# atmega2560-power_planes.net
KiCad netlist of a schematic drawn in EAGLE
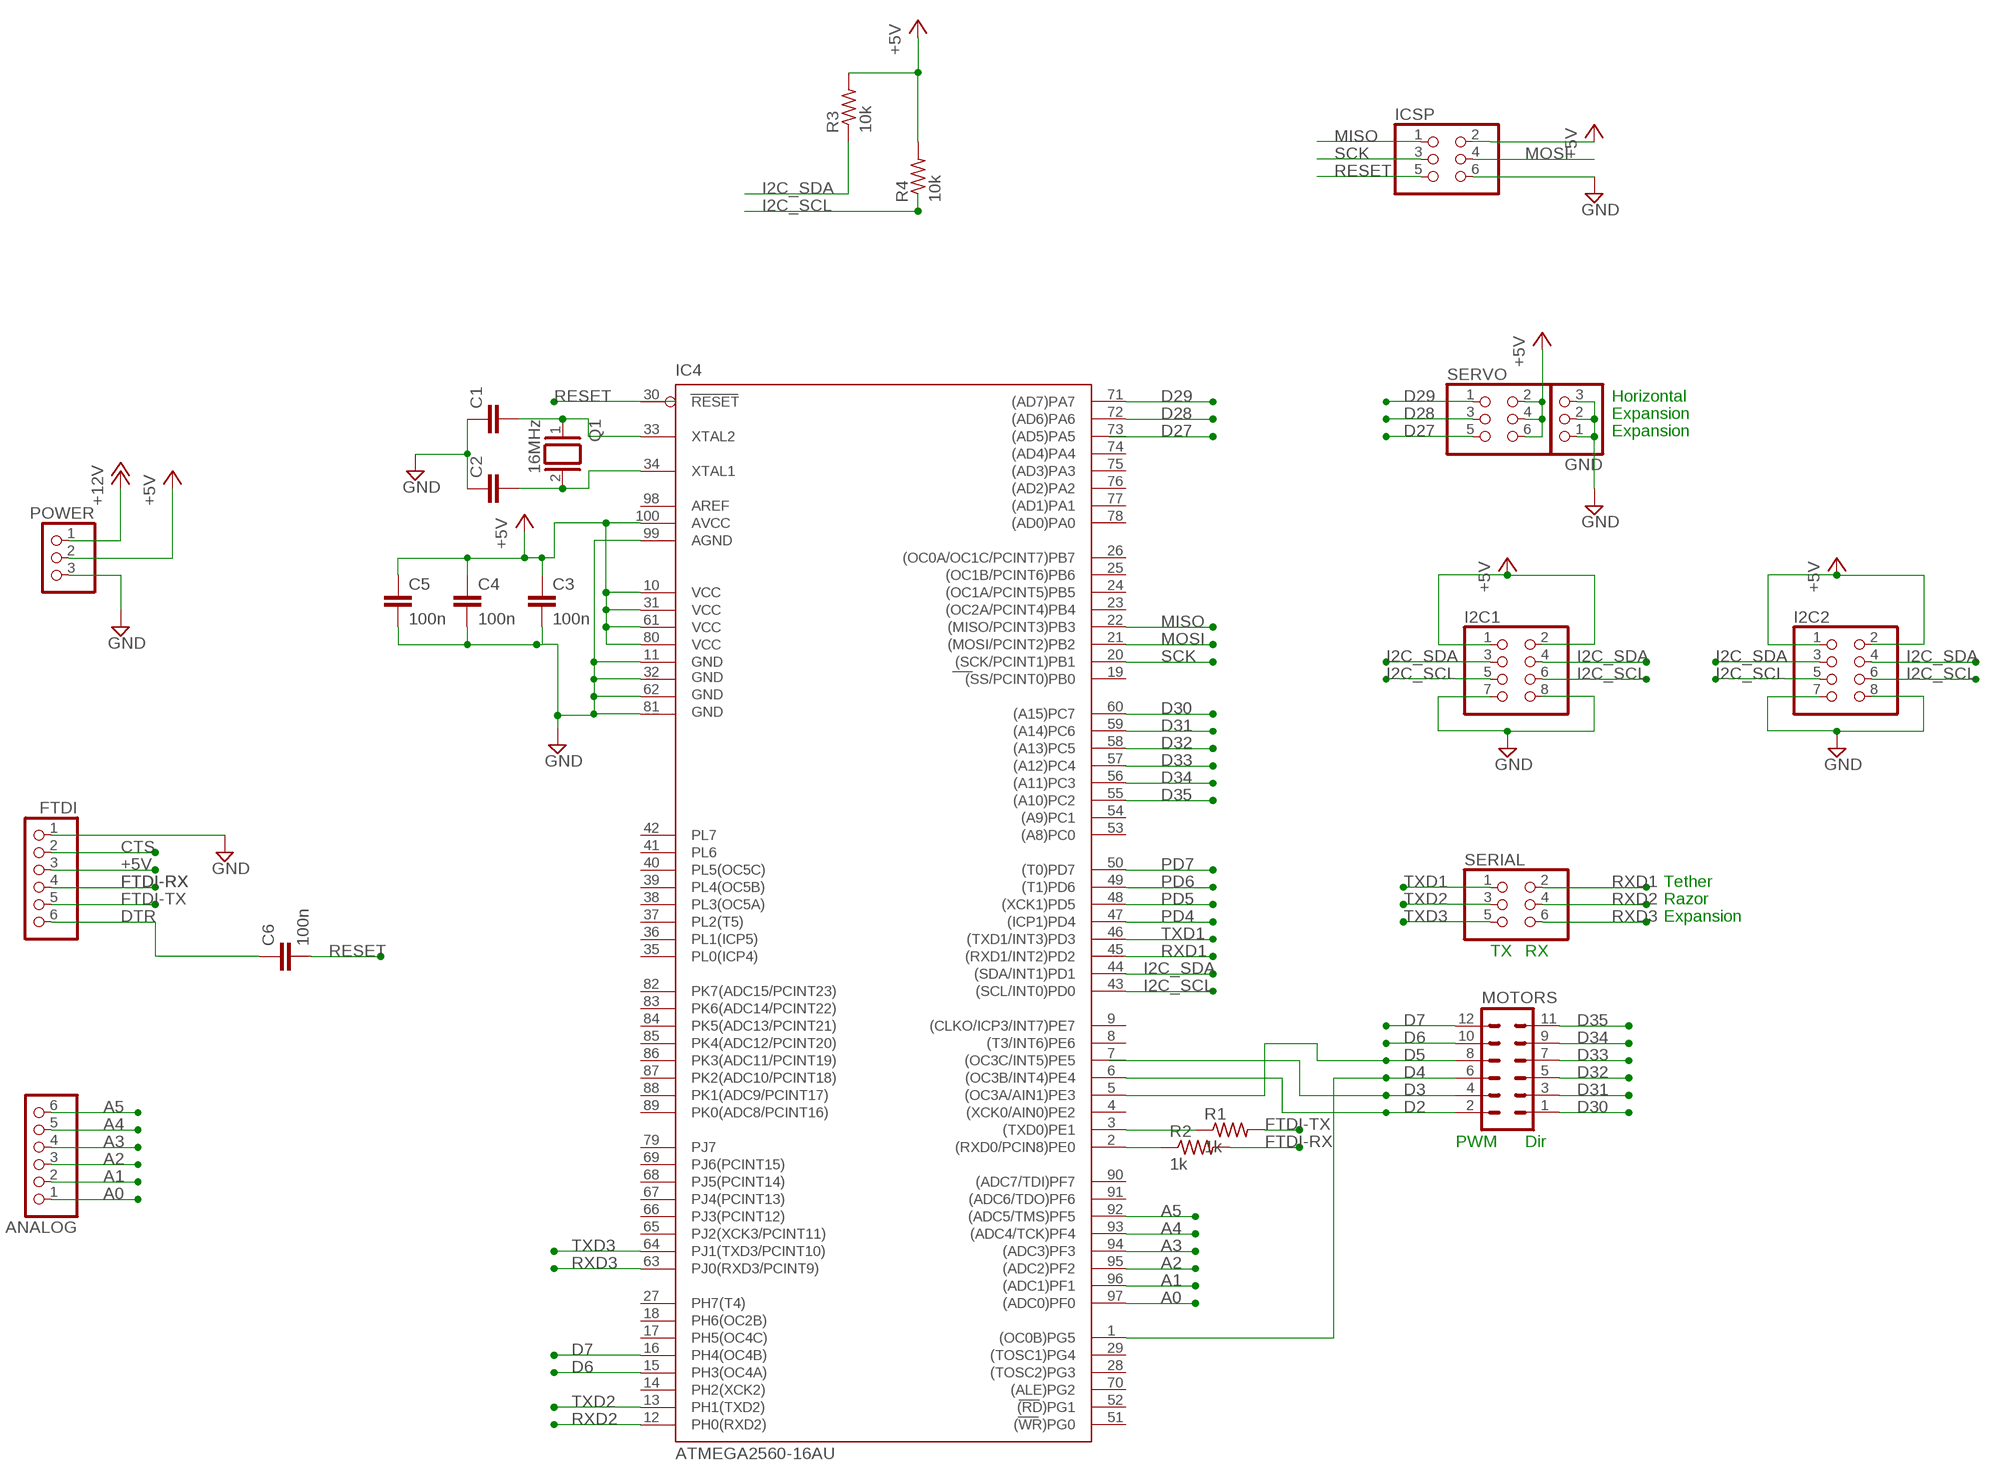
[diagram p0: schematic, sheet 1]

(export (version "E")
  (design (tool "Eeschema 10.0.6"))
  (components
    (comp (ref "ANALOG")
      (value "PINHD-1X6")
      (footprint "eagle-import:1X06")
      (libsource (lib "eagle-import") (part "PINHD-1X6"))
    )
    (comp (ref "C1")
      (value "C5/3.5")
      (footprint "eagle-import:C5B3.5")
      (libsource (lib "eagle-import") (part "C5/3.5"))
    )
    (comp (ref "C2")
      (value "C5/3.5")
      (footprint "eagle-import:C5B3.5")
      (libsource (lib "eagle-import") (part "C5/3.5"))
    )
    (comp (ref "C3")
      (value "100n")
      (footprint "eagle-import:C5B3.5")
      (libsource (lib "eagle-import") (part "C5/3.5"))
    )
    (comp (ref "C4")
      (value "100n")
      (footprint "eagle-import:C5B3.5")
      (libsource (lib "eagle-import") (part "C5/3.5"))
    )
    (comp (ref "C5")
      (value "100n")
      (footprint "eagle-import:C5B3.5")
      (libsource (lib "eagle-import") (part "C5/3.5"))
    )
    (comp (ref "C6")
      (value "100n")
      (footprint "eagle-import:C050-030X075")
      (libsource (lib "eagle-import") (part "C-EU050-030X075"))
    )
    (comp (ref "FTDI")
      (value "PINHD-1X6")
      (footprint "eagle-import:1X06")
      (libsource (lib "eagle-import") (part "PINHD-1X6"))
    )
    (comp (ref "GND")
      (value "PINHD-1X3")
      (footprint "eagle-import:1X03")
      (libsource (lib "eagle-import") (part "PINHD-1X3"))
    )
    (comp (ref "I2C1")
      (value "PINHD-2X4")
      (footprint "eagle-import:2X04")
      (libsource (lib "eagle-import") (part "PINHD-2X4"))
    )
    (comp (ref "I2C2")
      (value "PINHD-2X4")
      (footprint "eagle-import:2X04")
      (libsource (lib "eagle-import") (part "PINHD-2X4"))
    )
    (comp (ref "IC4")
      (value "ATMEGA2560-16AU")
      (footprint "eagle-import:TQFP100")
      (libsource (lib "eagle-import") (part "ATMEGAAU2560-16"))
    )
    (comp (ref "ICSP")
      (value "PINHD-2X3")
      (footprint "eagle-import:2X03")
      (libsource (lib "eagle-import") (part "PINHD-2X3"))
    )
    (comp (ref "MOTORS")
      (value "MA06-2")
      (footprint "eagle-import:MA06-2")
      (libsource (lib "eagle-import") (part "MA06-2"))
    )
    (comp (ref "POWER")
      (value "PINHD-1X3")
      (footprint "eagle-import:1X03")
      (libsource (lib "eagle-import") (part "PINHD-1X3"))
    )
    (comp (ref "Q1")
      (value "16MHz")
      (footprint "eagle-import:QS")
      (libsource (lib "eagle-import") (part "XTAL/S"))
    )
    (comp (ref "R1")
      (value "1k")
      (footprint "eagle-import:0207_7")
      (libsource (lib "eagle-import") (part "R-US_0207/7"))
    )
    (comp (ref "R2")
      (value "1k")
      (footprint "eagle-import:0207_7")
      (libsource (lib "eagle-import") (part "R-US_0207/7"))
    )
    (comp (ref "R3")
      (value "10k")
      (footprint "eagle-import:0207_7")
      (libsource (lib "eagle-import") (part "R-US_0207/7"))
    )
    (comp (ref "R4")
      (value "10k")
      (footprint "eagle-import:0207_7")
      (libsource (lib "eagle-import") (part "R-US_0207/7"))
    )
    (comp (ref "SERIAL")
      (value "PINHD-2X3")
      (footprint "eagle-import:2X03")
      (libsource (lib "eagle-import") (part "PINHD-2X3"))
    )
    (comp (ref "SERVO")
      (value "PINHD-2X3")
      (footprint "eagle-import:2X03")
      (libsource (lib "eagle-import") (part "PINHD-2X3"))
    )
  )
  (nets
    (net (code "1") (name "+5V") (class "Default")
      (node (ref "C3") (pin "1") (pinfunction "1_1") (pintype "passive"))
      (node (ref "C4") (pin "1") (pinfunction "1_1") (pintype "passive"))
      (node (ref "C5") (pin "1") (pinfunction "1_1") (pintype "passive"))
      (node (ref "FTDI") (pin "3") (pinfunction "3_3") (pintype "passive"))
      (node (ref "I2C1") (pin "1") (pinfunction "1_1") (pintype "passive"))
      (node (ref "I2C1") (pin "2") (pinfunction "2_2") (pintype "passive"))
      (node (ref "I2C2") (pin "1") (pinfunction "1_1") (pintype "passive"))
      (node (ref "I2C2") (pin "2") (pinfunction "2_2") (pintype "passive"))
      (node (ref "IC4") (pin "10") (pinfunction "VCC_10") (pintype "power_in"))
      (node (ref "IC4") (pin "100") (pinfunction "AVCC_100") (pintype "power_in"))
      (node (ref "IC4") (pin "31") (pinfunction "VCC1_31") (pintype "power_in"))
      (node (ref "IC4") (pin "61") (pinfunction "VCC2_61") (pintype "power_in"))
      (node (ref "IC4") (pin "80") (pinfunction "VCC3_80") (pintype "power_in"))
      (node (ref "ICSP") (pin "2") (pinfunction "2_2") (pintype "passive"))
      (node (ref "POWER") (pin "2") (pinfunction "2_2") (pintype "passive"))
      (node (ref "R3") (pin "2") (pinfunction "2_2") (pintype "passive"))
      (node (ref "R4") (pin "2") (pinfunction "2_2") (pintype "passive"))
      (node (ref "SERVO") (pin "2") (pinfunction "2_2") (pintype "passive"))
      (node (ref "SERVO") (pin "4") (pinfunction "4_4") (pintype "passive"))
      (node (ref "SERVO") (pin "6") (pinfunction "6_6") (pintype "passive"))
    )
    (net (code "2") (name "+12V") (class "Default")
      (node (ref "POWER") (pin "1") (pinfunction "1_1") (pintype "passive"))
    )
    (net (code "3") (name "/A0") (class "Default")
      (node (ref "ANALOG") (pin "1") (pinfunction "1_1") (pintype "passive"))
      (node (ref "IC4") (pin "97") (pinfunction "(ADC0)PF0_97") (pintype "bidirectional"))
    )
    (net (code "4") (name "/A1") (class "Default")
      (node (ref "ANALOG") (pin "2") (pinfunction "2_2") (pintype "passive"))
      (node (ref "IC4") (pin "96") (pinfunction "(ADC1)PF1_96") (pintype "bidirectional"))
    )
    (net (code "5") (name "/A2") (class "Default")
      (node (ref "ANALOG") (pin "3") (pinfunction "3_3") (pintype "passive"))
      (node (ref "IC4") (pin "95") (pinfunction "(ADC2)PF2_95") (pintype "bidirectional"))
    )
    (net (code "6") (name "/A3") (class "Default")
      (node (ref "ANALOG") (pin "4") (pinfunction "4_4") (pintype "passive"))
      (node (ref "IC4") (pin "94") (pinfunction "(ADC3)PF3_94") (pintype "bidirectional"))
    )
    (net (code "7") (name "/A4") (class "Default")
      (node (ref "ANALOG") (pin "5") (pinfunction "5_5") (pintype "passive"))
      (node (ref "IC4") (pin "93") (pinfunction "(ADC4/TCK)PF4_93") (pintype "bidirectional"))
    )
    (net (code "8") (name "/A5") (class "Default")
      (node (ref "ANALOG") (pin "6") (pinfunction "6_6") (pintype "passive"))
      (node (ref "IC4") (pin "92") (pinfunction "(ADC5/TMS)PF5_92") (pintype "bidirectional"))
    )
    (net (code "9") (name "/CTS") (class "Default")
      (node (ref "FTDI") (pin "2") (pinfunction "2_2") (pintype "passive"))
    )
    (net (code "10") (name "/D2") (class "Default")
      (node (ref "IC4") (pin "6") (pinfunction "(OC3B/INT4)PE4_6") (pintype "bidirectional"))
      (node (ref "MOTORS") (pin "2") (pinfunction "2_2") (pintype "passive"))
    )
    (net (code "11") (name "/D3") (class "Default")
      (node (ref "MOTORS") (pin "4") (pinfunction "4_4") (pintype "passive"))
    )
    (net (code "12") (name "/D4") (class "Default")
      (node (ref "IC4") (pin "1") (pinfunction "(OC0B)PG5_1") (pintype "bidirectional"))
      (node (ref "MOTORS") (pin "6") (pinfunction "6_6") (pintype "passive"))
    )
    (net (code "13") (name "/D5") (class "Default")
      (node (ref "IC4") (pin "5") (pinfunction "(OC3A/AIN1)PE3_5") (pintype "bidirectional"))
      (node (ref "MOTORS") (pin "8") (pinfunction "8_8") (pintype "passive"))
    )
    (net (code "14") (name "/D6") (class "Default")
      (node (ref "IC4") (pin "15") (pinfunction "PH3(OC4A)_15") (pintype "bidirectional"))
      (node (ref "MOTORS") (pin "10") (pinfunction "10_10") (pintype "passive"))
    )
    (net (code "15") (name "/D7") (class "Default")
      (node (ref "IC4") (pin "16") (pinfunction "PH4(OC4B)_16") (pintype "bidirectional"))
      (node (ref "MOTORS") (pin "12") (pinfunction "12_12") (pintype "passive"))
    )
    (net (code "16") (name "/D27") (class "Default")
      (node (ref "SERVO") (pin "5") (pinfunction "5_5") (pintype "passive"))
    )
    (net (code "17") (name "/D28") (class "Default")
      (node (ref "IC4") (pin "72") (pinfunction "(AD6)PA6_72") (pintype "bidirectional"))
      (node (ref "SERVO") (pin "3") (pinfunction "3_3") (pintype "passive"))
    )
    (net (code "18") (name "/D29") (class "Default")
      (node (ref "IC4") (pin "71") (pinfunction "(AD7)PA7_71") (pintype "bidirectional"))
      (node (ref "SERVO") (pin "1") (pinfunction "1_1") (pintype "passive"))
    )
    (net (code "19") (name "/D30") (class "Default")
      (node (ref "IC4") (pin "60") (pinfunction "(A15)PC7_60") (pintype "bidirectional"))
      (node (ref "MOTORS") (pin "1") (pinfunction "1_1") (pintype "passive"))
    )
    (net (code "20") (name "/D31") (class "Default")
      (node (ref "IC4") (pin "59") (pinfunction "(A14)PC6_59") (pintype "bidirectional"))
      (node (ref "MOTORS") (pin "3") (pinfunction "3_3") (pintype "passive"))
    )
    (net (code "21") (name "/D32") (class "Default")
      (node (ref "IC4") (pin "58") (pinfunction "(A13)PC5_58") (pintype "bidirectional"))
      (node (ref "MOTORS") (pin "5") (pinfunction "5_5") (pintype "passive"))
    )
    (net (code "22") (name "/D33") (class "Default")
      (node (ref "IC4") (pin "57") (pinfunction "(A12)PC4_57") (pintype "bidirectional"))
      (node (ref "MOTORS") (pin "7") (pinfunction "7_7") (pintype "passive"))
    )
    (net (code "23") (name "/D34") (class "Default")
      (node (ref "IC4") (pin "56") (pinfunction "(A11)PC3_56") (pintype "bidirectional"))
      (node (ref "MOTORS") (pin "9") (pinfunction "9_9") (pintype "passive"))
    )
    (net (code "24") (name "/D35") (class "Default")
      (node (ref "IC4") (pin "55") (pinfunction "(A10)PC2_55") (pintype "bidirectional"))
      (node (ref "MOTORS") (pin "11") (pinfunction "11_11") (pintype "passive"))
    )
    (net (code "25") (name "/DTR") (class "Default")
      (node (ref "C6") (pin "1") (pinfunction "1_1") (pintype "passive"))
      (node (ref "FTDI") (pin "6") (pinfunction "6_6") (pintype "passive"))
    )
    (net (code "26") (name "/FTDI-RX") (class "Default")
      (node (ref "FTDI") (pin "4") (pinfunction "4_4") (pintype "passive"))
      (node (ref "R2") (pin "2") (pinfunction "2_2") (pintype "passive"))
    )
    (net (code "27") (name "/FTDI-TX") (class "Default")
      (node (ref "FTDI") (pin "5") (pinfunction "5_5") (pintype "passive"))
      (node (ref "R1") (pin "2") (pinfunction "2_2") (pintype "passive"))
    )
    (net (code "28") (name "/I2C_SCL") (class "Default")
      (node (ref "I2C1") (pin "5") (pinfunction "5_5") (pintype "passive"))
      (node (ref "I2C1") (pin "6") (pinfunction "6_6") (pintype "passive"))
      (node (ref "I2C2") (pin "5") (pinfunction "5_5") (pintype "passive"))
      (node (ref "I2C2") (pin "6") (pinfunction "6_6") (pintype "passive"))
      (node (ref "IC4") (pin "43") (pinfunction "(SCL/INT0)PD0_43") (pintype "bidirectional"))
      (node (ref "R4") (pin "1") (pinfunction "1_1") (pintype "passive"))
    )
    (net (code "29") (name "/I2C_SDA") (class "Default")
      (node (ref "I2C1") (pin "3") (pinfunction "3_3") (pintype "passive"))
      (node (ref "I2C1") (pin "4") (pinfunction "4_4") (pintype "passive"))
      (node (ref "I2C2") (pin "3") (pinfunction "3_3") (pintype "passive"))
      (node (ref "I2C2") (pin "4") (pinfunction "4_4") (pintype "passive"))
      (node (ref "IC4") (pin "44") (pinfunction "(SDA/INT1)PD1_44") (pintype "bidirectional"))
      (node (ref "R3") (pin "1") (pinfunction "1_1") (pintype "passive"))
    )
    (net (code "30") (name "/MISO") (class "Default")
      (node (ref "IC4") (pin "22") (pinfunction "(MISO/PCINT3)PB3_22") (pintype "bidirectional"))
      (node (ref "ICSP") (pin "1") (pinfunction "1_1") (pintype "passive"))
    )
    (net (code "31") (name "/MOSI") (class "Default")
      (node (ref "IC4") (pin "21") (pinfunction "(MOSI/PCINT2)PB2_21") (pintype "bidirectional"))
      (node (ref "ICSP") (pin "4") (pinfunction "4_4") (pintype "passive"))
    )
    (net (code "32") (name "/PD4") (class "Default")
      (node (ref "IC4") (pin "47") (pinfunction "(ICP1)PD4_47") (pintype "bidirectional"))
    )
    (net (code "33") (name "/PD5") (class "Default")
      (node (ref "IC4") (pin "48") (pinfunction "(XCK1)PD5_48") (pintype "bidirectional"))
    )
    (net (code "34") (name "/PD6") (class "Default")
      (node (ref "IC4") (pin "49") (pinfunction "(T1)PD6_49") (pintype "bidirectional"))
    )
    (net (code "35") (name "/PD7") (class "Default")
      (node (ref "IC4") (pin "50") (pinfunction "(T0)PD7_50") (pintype "bidirectional"))
    )
    (net (code "36") (name "/RESET") (class "Default")
      (node (ref "C6") (pin "2") (pinfunction "2_2") (pintype "passive"))
      (node (ref "ICSP") (pin "5") (pinfunction "5_5") (pintype "passive"))
    )
    (net (code "37") (name "/RXD1") (class "Default")
      (node (ref "IC4") (pin "45") (pinfunction "(RXD1/INT2)PD2_45") (pintype "bidirectional"))
      (node (ref "SERIAL") (pin "2") (pinfunction "2_2") (pintype "passive"))
    )
    (net (code "38") (name "/RXD2") (class "Default")
      (node (ref "IC4") (pin "12") (pinfunction "PH0(RXD2)_12") (pintype "bidirectional"))
      (node (ref "SERIAL") (pin "4") (pinfunction "4_4") (pintype "passive"))
    )
    (net (code "39") (name "/RXD3") (class "Default")
      (node (ref "IC4") (pin "63") (pinfunction "PJ0(RXD3/PCINT9)_63") (pintype "bidirectional"))
      (node (ref "SERIAL") (pin "6") (pinfunction "6_6") (pintype "passive"))
    )
    (net (code "40") (name "/SCK") (class "Default")
      (node (ref "IC4") (pin "20") (pinfunction "(SCK/PCINT1)PB1_20") (pintype "bidirectional"))
      (node (ref "ICSP") (pin "3") (pinfunction "3_3") (pintype "passive"))
    )
    (net (code "41") (name "/TXD1") (class "Default")
      (node (ref "IC4") (pin "46") (pinfunction "(TXD1/INT3)PD3_46") (pintype "bidirectional"))
      (node (ref "SERIAL") (pin "1") (pinfunction "1_1") (pintype "passive"))
    )
    (net (code "42") (name "/TXD2") (class "Default")
      (node (ref "IC4") (pin "13") (pinfunction "PH1(TXD2)_13") (pintype "bidirectional"))
      (node (ref "SERIAL") (pin "3") (pinfunction "3_3") (pintype "passive"))
    )
    (net (code "43") (name "/TXD3") (class "Default")
      (node (ref "IC4") (pin "64") (pinfunction "PJ1(TXD3/PCINT10)_64") (pintype "bidirectional"))
      (node (ref "SERIAL") (pin "5") (pinfunction "5_5") (pintype "passive"))
    )
    (net (code "44") (name "GND") (class "Default")
      (node (ref "C1") (pin "1") (pinfunction "1_1") (pintype "passive"))
      (node (ref "C2") (pin "1") (pinfunction "1_1") (pintype "passive"))
      (node (ref "C3") (pin "2") (pinfunction "2_2") (pintype "passive"))
      (node (ref "C4") (pin "2") (pinfunction "2_2") (pintype "passive"))
      (node (ref "C5") (pin "2") (pinfunction "2_2") (pintype "passive"))
      (node (ref "FTDI") (pin "1") (pinfunction "1_1") (pintype "passive"))
      (node (ref "GND") (pin "1") (pinfunction "1_1") (pintype "passive"))
      (node (ref "GND") (pin "2") (pinfunction "2_2") (pintype "passive"))
      (node (ref "GND") (pin "3") (pinfunction "3_3") (pintype "passive"))
      (node (ref "I2C1") (pin "7") (pinfunction "7_7") (pintype "passive"))
      (node (ref "I2C1") (pin "8") (pinfunction "8_8") (pintype "passive"))
      (node (ref "I2C2") (pin "7") (pinfunction "7_7") (pintype "passive"))
      (node (ref "I2C2") (pin "8") (pinfunction "8_8") (pintype "passive"))
      (node (ref "IC4") (pin "11") (pinfunction "GND_11") (pintype "power_in"))
      (node (ref "IC4") (pin "32") (pinfunction "GND1_32") (pintype "power_in"))
      (node (ref "IC4") (pin "62") (pinfunction "GND2_62") (pintype "power_in"))
      (node (ref "IC4") (pin "81") (pinfunction "GND3_81") (pintype "power_in"))
      (node (ref "IC4") (pin "99") (pinfunction "AGND_99") (pintype "power_in"))
      (node (ref "ICSP") (pin "6") (pinfunction "6_6") (pintype "passive"))
      (node (ref "POWER") (pin "3") (pinfunction "3_3") (pintype "passive"))
    )
    (net (code "45") (name "Net-(IC4-(RXD0{slash}PCIN8)PE0)") (class "Default")
      (node (ref "IC4") (pin "2") (pinfunction "(RXD0/PCIN8)PE0_2") (pintype "bidirectional"))
      (node (ref "R2") (pin "1") (pinfunction "1_1") (pintype "passive"))
    )
    (net (code "46") (name "Net-(IC4-(TXD0)PE1)") (class "Default")
      (node (ref "IC4") (pin "3") (pinfunction "(TXD0)PE1_3") (pintype "bidirectional"))
      (node (ref "R1") (pin "1") (pinfunction "1_1") (pintype "passive"))
    )
    (net (code "47") (name "Net-(IC4-XTAL1)") (class "Default")
      (node (ref "C2") (pin "2") (pinfunction "2_2") (pintype "passive"))
      (node (ref "IC4") (pin "34") (pinfunction "XTAL1_34") (pintype "input"))
      (node (ref "Q1") (pin "2") (pinfunction "2_2") (pintype "passive"))
    )
    (net (code "48") (name "Net-(IC4-XTAL2)") (class "Default")
      (node (ref "C1") (pin "2") (pinfunction "2_2") (pintype "passive"))
      (node (ref "IC4") (pin "33") (pinfunction "XTAL2_33") (pintype "output"))
      (node (ref "Q1") (pin "1") (pinfunction "1_1") (pintype "passive"))
    )
    (net (code "49") (name "unconnected-(IC4-(A8)PC0-Pad53)") (class "Default")
      (node (ref "IC4") (pin "53") (pinfunction "(A8)PC0_53") (pintype "bidirectional"))
    )
    (net (code "50") (name "unconnected-(IC4-(A9)PC1-Pad54)") (class "Default")
      (node (ref "IC4") (pin "54") (pinfunction "(A9)PC1_54") (pintype "bidirectional"))
    )
    (net (code "51") (name "unconnected-(IC4-(AD0)PA0-Pad78)") (class "Default")
      (node (ref "IC4") (pin "78") (pinfunction "(AD0)PA0_78") (pintype "bidirectional"))
    )
    (net (code "52") (name "unconnected-(IC4-(AD1)PA1-Pad77)") (class "Default")
      (node (ref "IC4") (pin "77") (pinfunction "(AD1)PA1_77") (pintype "bidirectional"))
    )
    (net (code "53") (name "unconnected-(IC4-(AD2)PA2-Pad76)") (class "Default")
      (node (ref "IC4") (pin "76") (pinfunction "(AD2)PA2_76") (pintype "bidirectional"))
    )
    (net (code "54") (name "unconnected-(IC4-(AD3)PA3-Pad75)") (class "Default")
      (node (ref "IC4") (pin "75") (pinfunction "(AD3)PA3_75") (pintype "bidirectional"))
    )
    (net (code "55") (name "unconnected-(IC4-(AD4)PA4-Pad74)") (class "Default")
      (node (ref "IC4") (pin "74") (pinfunction "(AD4)PA4_74") (pintype "bidirectional"))
    )
    (net (code "56") (name "unconnected-(IC4-(AD5)PA5-Pad73)") (class "Default")
      (node (ref "IC4") (pin "73") (pinfunction "(AD5)PA5_73") (pintype "bidirectional"))
    )
    (net (code "57") (name "unconnected-(IC4-(ADC6{slash}TDO)PF6-Pad91)") (class "Default")
      (node (ref "IC4") (pin "91") (pinfunction "(ADC6/TDO)PF6_91") (pintype "bidirectional"))
    )
    (net (code "58") (name "unconnected-(IC4-(ADC7{slash}TDI)PF7-Pad90)") (class "Default")
      (node (ref "IC4") (pin "90") (pinfunction "(ADC7/TDI)PF7_90") (pintype "bidirectional"))
    )
    (net (code "59") (name "unconnected-(IC4-(ALE)PG2-Pad70)") (class "Default")
      (node (ref "IC4") (pin "70") (pinfunction "(ALE)PG2_70") (pintype "bidirectional"))
    )
    (net (code "60") (name "unconnected-(IC4-(CLKO{slash}ICP3{slash}INT7)PE7-Pad9)") (class "Default")
      (node (ref "IC4") (pin "9") (pinfunction "(CLKO/ICP3/INT7)PE7_9") (pintype "bidirectional"))
    )
    (net (code "61") (name "unconnected-(IC4-(OC0A{slash}OC1C{slash}PCINT7)PB7-Pad26)") (class "Default")
      (node (ref "IC4") (pin "26") (pinfunction "(OC0A/OC1C/PCINT7)PB7_26") (pintype "bidirectional"))
    )
    (net (code "62") (name "unconnected-(IC4-(OC1A{slash}PCINT5)PB5-Pad24)") (class "Default")
      (node (ref "IC4") (pin "24") (pinfunction "(OC1A/PCINT5)PB5_24") (pintype "bidirectional"))
    )
    (net (code "63") (name "unconnected-(IC4-(OC1B{slash}PCINT6)PB6-Pad25)") (class "Default")
      (node (ref "IC4") (pin "25") (pinfunction "(OC1B/PCINT6)PB6_25") (pintype "bidirectional"))
    )
    (net (code "64") (name "unconnected-(IC4-(OC2A{slash}PCINT4)PB4-Pad23)") (class "Default")
      (node (ref "IC4") (pin "23") (pinfunction "(OC2A/PCINT4)PB4_23") (pintype "bidirectional"))
    )
    (net (code "65") (name "unconnected-(IC4-(OC3C{slash}INT5)PE5-Pad7)") (class "Default")
      (node (ref "IC4") (pin "7") (pinfunction "(OC3C/INT5)PE5_7") (pintype "bidirectional"))
    )
    (net (code "66") (name "unconnected-(IC4-(RD)PG1-Pad52)") (class "Default")
      (node (ref "IC4") (pin "52") (pinfunction "(RD)PG1_52") (pintype "bidirectional"))
    )
    (net (code "67") (name "unconnected-(IC4-(SS{slash}PCINT0)PB0-Pad19)") (class "Default")
      (node (ref "IC4") (pin "19") (pinfunction "(SS/PCINT0)PB0_19") (pintype "bidirectional"))
    )
    (net (code "68") (name "unconnected-(IC4-(T3{slash}INT6)PE6-Pad8)") (class "Default")
      (node (ref "IC4") (pin "8") (pinfunction "(T3/INT6)PE6_8") (pintype "bidirectional"))
    )
    (net (code "69") (name "unconnected-(IC4-(TOSC1)PG4-Pad29)") (class "Default")
      (node (ref "IC4") (pin "29") (pinfunction "(TOSC1)PG4_29") (pintype "bidirectional"))
    )
    (net (code "70") (name "unconnected-(IC4-(TOSC2)PG3-Pad28)") (class "Default")
      (node (ref "IC4") (pin "28") (pinfunction "(TOSC2)PG3_28") (pintype "bidirectional"))
    )
    (net (code "71") (name "unconnected-(IC4-(WR)PG0-Pad51)") (class "Default")
      (node (ref "IC4") (pin "51") (pinfunction "(WR)PG0_51") (pintype "bidirectional"))
    )
    (net (code "72") (name "unconnected-(IC4-(XCK0{slash}AIN0)PE2-Pad4)") (class "Default")
      (node (ref "IC4") (pin "4") (pinfunction "(XCK0/AIN0)PE2_4") (pintype "bidirectional"))
    )
    (net (code "73") (name "unconnected-(IC4-AREF-Pad98)") (class "Default")
      (node (ref "IC4") (pin "98") (pinfunction "AREF_98") (pintype "bidirectional"))
    )
    (net (code "74") (name "unconnected-(IC4-PH2(XCK2)-Pad14)") (class "Default")
      (node (ref "IC4") (pin "14") (pinfunction "PH2(XCK2)_14") (pintype "bidirectional"))
    )
    (net (code "75") (name "unconnected-(IC4-PH5(OC4C)-Pad17)") (class "Default")
      (node (ref "IC4") (pin "17") (pinfunction "PH5(OC4C)_17") (pintype "bidirectional"))
    )
    (net (code "76") (name "unconnected-(IC4-PH6(OC2B)-Pad18)") (class "Default")
      (node (ref "IC4") (pin "18") (pinfunction "PH6(OC2B)_18") (pintype "bidirectional"))
    )
    (net (code "77") (name "unconnected-(IC4-PH7(T4)-Pad27)") (class "Default")
      (node (ref "IC4") (pin "27") (pinfunction "PH7(T4)_27") (pintype "bidirectional"))
    )
    (net (code "78") (name "unconnected-(IC4-PJ2(XCK3{slash}PCINT11)-Pad65)") (class "Default")
      (node (ref "IC4") (pin "65") (pinfunction "PJ2(XCK3/PCINT11)_65") (pintype "bidirectional"))
    )
    (net (code "79") (name "unconnected-(IC4-PJ3(PCINT12)-Pad66)") (class "Default")
      (node (ref "IC4") (pin "66") (pinfunction "PJ3(PCINT12)_66") (pintype "bidirectional"))
    )
    (net (code "80") (name "unconnected-(IC4-PJ4(PCINT13)-Pad67)") (class "Default")
      (node (ref "IC4") (pin "67") (pinfunction "PJ4(PCINT13)_67") (pintype "bidirectional"))
    )
    (net (code "81") (name "unconnected-(IC4-PJ5(PCINT14)-Pad68)") (class "Default")
      (node (ref "IC4") (pin "68") (pinfunction "PJ5(PCINT14)_68") (pintype "bidirectional"))
    )
    (net (code "82") (name "unconnected-(IC4-PJ6(PCINT15)-Pad69)") (class "Default")
      (node (ref "IC4") (pin "69") (pinfunction "PJ6(PCINT15)_69") (pintype "bidirectional"))
    )
    (net (code "83") (name "unconnected-(IC4-PJ7-Pad79)") (class "Default")
      (node (ref "IC4") (pin "79") (pinfunction "PJ7_79") (pintype "bidirectional"))
    )
    (net (code "84") (name "unconnected-(IC4-PK0(ADC8{slash}PCINT16)-Pad89)") (class "Default")
      (node (ref "IC4") (pin "89") (pinfunction "PK0(ADC8/PCINT16)_89") (pintype "bidirectional"))
    )
    (net (code "85") (name "unconnected-(IC4-PK1(ADC9{slash}PCINT17)-Pad88)") (class "Default")
      (node (ref "IC4") (pin "88") (pinfunction "PK1(ADC9/PCINT17)_88") (pintype "bidirectional"))
    )
    (net (code "86") (name "unconnected-(IC4-PK2(ADC10{slash}PCINT18)-Pad87)") (class "Default")
      (node (ref "IC4") (pin "87") (pinfunction "PK2(ADC10/PCINT18)_87") (pintype "bidirectional"))
    )
    (net (code "87") (name "unconnected-(IC4-PK3(ADC11{slash}PCINT19)-Pad86)") (class "Default")
      (node (ref "IC4") (pin "86") (pinfunction "PK3(ADC11/PCINT19)_86") (pintype "bidirectional"))
    )
    (net (code "88") (name "unconnected-(IC4-PK4(ADC12{slash}PCINT20)-Pad85)") (class "Default")
      (node (ref "IC4") (pin "85") (pinfunction "PK4(ADC12/PCINT20)_85") (pintype "bidirectional"))
    )
    (net (code "89") (name "unconnected-(IC4-PK5(ADC13{slash}PCINT21)-Pad84)") (class "Default")
      (node (ref "IC4") (pin "84") (pinfunction "PK5(ADC13/PCINT21)_84") (pintype "bidirectional"))
    )
    (net (code "90") (name "unconnected-(IC4-PK6(ADC14{slash}PCINT22)-Pad83)") (class "Default")
      (node (ref "IC4") (pin "83") (pinfunction "PK6(ADC14/PCINT22)_83") (pintype "bidirectional"))
    )
    (net (code "91") (name "unconnected-(IC4-PK7(ADC15{slash}PCINT23)-Pad82)") (class "Default")
      (node (ref "IC4") (pin "82") (pinfunction "PK7(ADC15/PCINT23)_82") (pintype "bidirectional"))
    )
    (net (code "92") (name "unconnected-(IC4-PL0(ICP4)-Pad35)") (class "Default")
      (node (ref "IC4") (pin "35") (pinfunction "PL0(ICP4)_35") (pintype "bidirectional"))
    )
    (net (code "93") (name "unconnected-(IC4-PL1(ICP5)-Pad36)") (class "Default")
      (node (ref "IC4") (pin "36") (pinfunction "PL1(ICP5)_36") (pintype "bidirectional"))
    )
    (net (code "94") (name "unconnected-(IC4-PL2(T5)-Pad37)") (class "Default")
      (node (ref "IC4") (pin "37") (pinfunction "PL2(T5)_37") (pintype "bidirectional"))
    )
    (net (code "95") (name "unconnected-(IC4-PL3(OC5A)-Pad38)") (class "Default")
      (node (ref "IC4") (pin "38") (pinfunction "PL3(OC5A)_38") (pintype "bidirectional"))
    )
    (net (code "96") (name "unconnected-(IC4-PL4(OC5B)-Pad39)") (class "Default")
      (node (ref "IC4") (pin "39") (pinfunction "PL4(OC5B)_39") (pintype "bidirectional"))
    )
    (net (code "97") (name "unconnected-(IC4-PL5(OC5C)-Pad40)") (class "Default")
      (node (ref "IC4") (pin "40") (pinfunction "PL5(OC5C)_40") (pintype "bidirectional"))
    )
    (net (code "98") (name "unconnected-(IC4-PL6-Pad41)") (class "Default")
      (node (ref "IC4") (pin "41") (pinfunction "PL6_41") (pintype "bidirectional"))
    )
    (net (code "99") (name "unconnected-(IC4-PL7-Pad42)") (class "Default")
      (node (ref "IC4") (pin "42") (pinfunction "PL7_42") (pintype "bidirectional"))
    )
    (net (code "100") (name "unconnected-(IC4-RESET-Pad30)") (class "Default")
      (node (ref "IC4") (pin "30") (pinfunction "RESET_30") (pintype "input"))
    )
  )
)
